# ESP32_radio_rev1_0.net
KiCad netlist of a schematic drawn in EAGLE
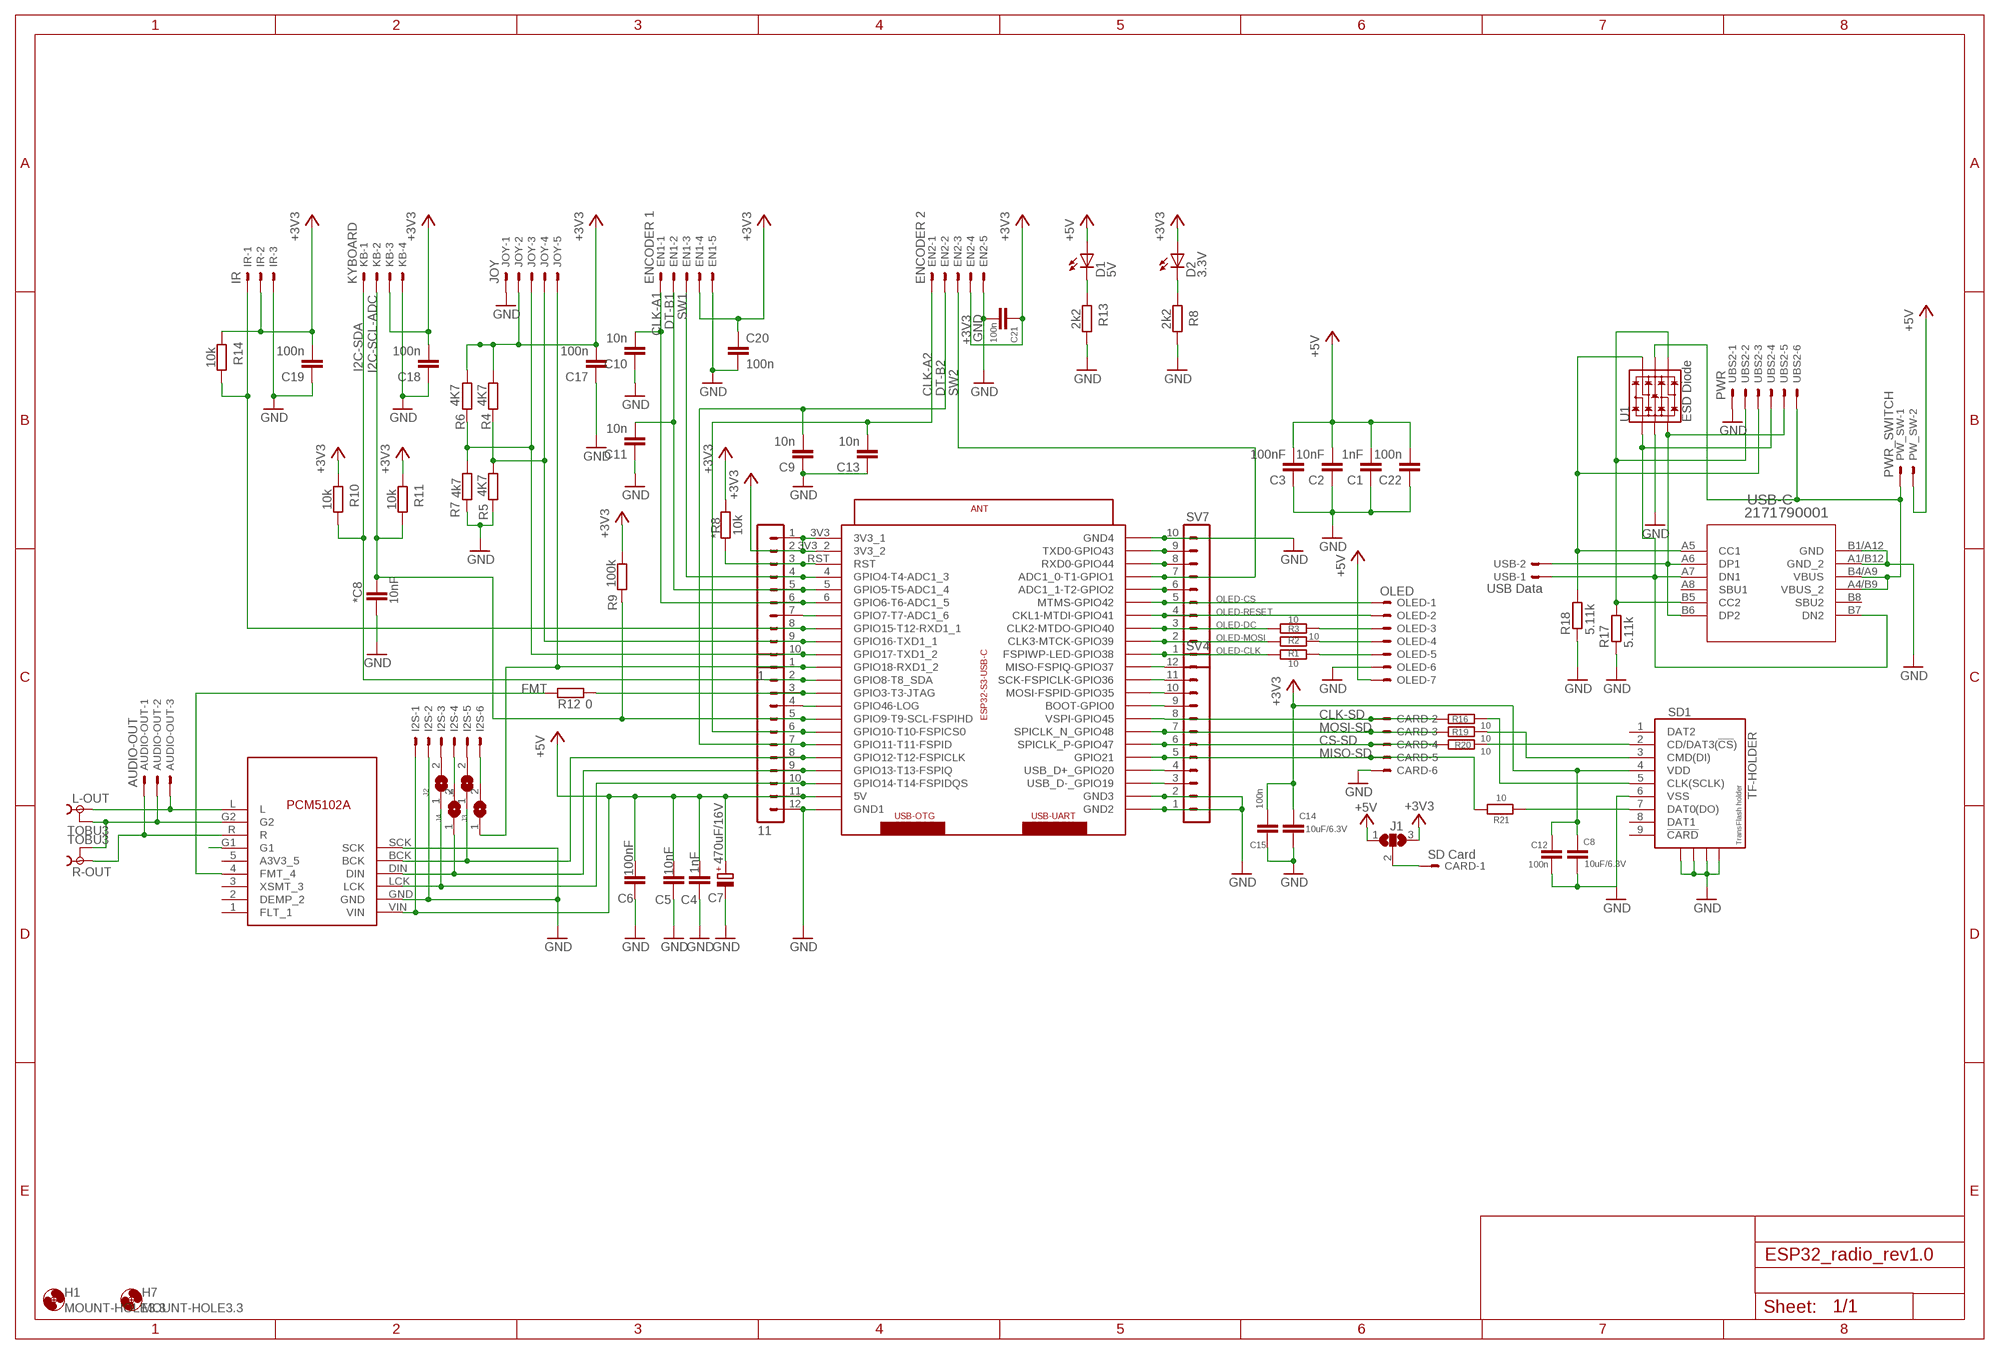
[diagram p0: schematic, sheet 1]

(export (version "E")
  (design (tool "Eeschema 10.0.6"))
  (components
    (comp (ref "*C8")
      (value "10nF")
      (footprint "eagle-import:C0603")
      (libsource (lib "eagle-import") (part "C-EUC0603"))
    )
    (comp (ref "*R8")
      (value "10k")
      (footprint "eagle-import:R0603")
      (libsource (lib "eagle-import") (part "R-EU_R0603"))
    )
    (comp (ref "1")
      (value "MA10-1")
      (footprint "eagle-import:MA10-1")
      (libsource (lib "eagle-import") (part "MA10-1"))
    )
    (comp (ref "11")
      (value "MA12-1")
      (footprint "eagle-import:MA12-1")
      (libsource (lib "eagle-import") (part "MA12-1"))
    )
    (comp (ref "AUDIO-OUT")
      (value "AUDIO-OUT")
      (footprint "eagle-import:JST-XH-03-PACKAGE-LONG-PAD")
      (libsource (lib "eagle-import") (part "JST-XH-03-PIN-LONG-PAD"))
    )
    (comp (ref "C1")
      (value "1nF")
      (footprint "eagle-import:C0603")
      (libsource (lib "eagle-import") (part "C-EUC0603"))
    )
    (comp (ref "C2")
      (value "10nF")
      (footprint "eagle-import:C0603")
      (libsource (lib "eagle-import") (part "C-EUC0603"))
    )
    (comp (ref "C3")
      (value "100nF")
      (footprint "eagle-import:C0603")
      (libsource (lib "eagle-import") (part "C-EUC0603"))
    )
    (comp (ref "C4")
      (value "1nF")
      (footprint "eagle-import:C0603")
      (libsource (lib "eagle-import") (part "C-EUC0603"))
    )
    (comp (ref "C5")
      (value "10nF")
      (footprint "eagle-import:C0603")
      (libsource (lib "eagle-import") (part "C-EUC0603"))
    )
    (comp (ref "C6")
      (value "100nF")
      (footprint "eagle-import:C0603")
      (libsource (lib "eagle-import") (part "C-EUC0603"))
    )
    (comp (ref "C7")
      (value "470uF/16V")
      (footprint "eagle-import:150CLZ-1010")
      (libsource (lib "eagle-import") (part "CPOL-EU150CLZ-1010"))
    )
    (comp (ref "C8")
      (value "10uF/6.3V")
      (footprint "eagle-import:C1210")
      (libsource (lib "eagle-import") (part "C-EUC1210"))
    )
    (comp (ref "C9")
      (value "10n")
      (footprint "eagle-import:C0603")
      (libsource (lib "eagle-import") (part "C-EUC0603"))
    )
    (comp (ref "C10")
      (value "10n")
      (footprint "eagle-import:C0603")
      (libsource (lib "eagle-import") (part "C-EUC0603"))
    )
    (comp (ref "C11")
      (value "10n")
      (footprint "eagle-import:C0603")
      (libsource (lib "eagle-import") (part "C-EUC0603"))
    )
    (comp (ref "C12")
      (value "100n")
      (footprint "eagle-import:C0603")
      (libsource (lib "eagle-import") (part "C-EUC0603"))
    )
    (comp (ref "C13")
      (value "10n")
      (footprint "eagle-import:C0603")
      (libsource (lib "eagle-import") (part "C-EUC0603"))
    )
    (comp (ref "C14")
      (value "10uF/6.3V")
      (footprint "eagle-import:C1210")
      (libsource (lib "eagle-import") (part "C-EUC1210"))
    )
    (comp (ref "C15")
      (value "100n")
      (footprint "eagle-import:C0603")
      (libsource (lib "eagle-import") (part "C-EUC0603"))
    )
    (comp (ref "C17")
      (value "100n")
      (footprint "eagle-import:C0603")
      (libsource (lib "eagle-import") (part "C-EUC0603"))
    )
    (comp (ref "C18")
      (value "100n")
      (footprint "eagle-import:C0603")
      (libsource (lib "eagle-import") (part "C-EUC0603"))
    )
    (comp (ref "C19")
      (value "100n")
      (footprint "eagle-import:C0603")
      (libsource (lib "eagle-import") (part "C-EUC0603"))
    )
    (comp (ref "C20")
      (value "100n")
      (footprint "eagle-import:C0603")
      (libsource (lib "eagle-import") (part "C-EUC0603"))
    )
    (comp (ref "C21")
      (value "100n")
      (footprint "eagle-import:C0603")
      (libsource (lib "eagle-import") (part "C-EUC0603"))
    )
    (comp (ref "C22")
      (value "100n")
      (footprint "eagle-import:C0603")
      (libsource (lib "eagle-import") (part "C-EUC0603"))
    )
    (comp (ref "CARD")
      (value "SD Card")
      (footprint "eagle-import:JST-XH-06-PACKAGE-LONG-PAD")
      (libsource (lib "eagle-import") (part "JST-XH-06-PIN-LONG-PAD"))
    )
    (comp (ref "D1")
      (value "5V")
      (footprint "eagle-import:CHIP-LED0805")
      (libsource (lib "eagle-import") (part "LEDCHIP-LED0805"))
    )
    (comp (ref "D2")
      (value "3.3V")
      (footprint "eagle-import:CHIP-LED0805")
      (libsource (lib "eagle-import") (part "LEDCHIP-LED0805"))
    )
    (comp (ref "EN1")
      (value "ENCODER 1")
      (footprint "eagle-import:JST-XH-05-PACKAGE-LONG-PAD")
      (libsource (lib "eagle-import") (part "JST-XH-05-PIN-LONG-PAD"))
    )
    (comp (ref "EN2")
      (value "ENCODER 2")
      (footprint "eagle-import:JST-XH-05-PACKAGE-LONG-PAD")
      (libsource (lib "eagle-import") (part "JST-XH-05-PIN-LONG-PAD"))
    )
    (comp (ref "H1")
      (value "MOUNT-HOLE3.3")
      (footprint "eagle-import:3,3")
      (libsource (lib "eagle-import") (part "MOUNT-HOLE3.3"))
    )
    (comp (ref "H7")
      (value "MOUNT-HOLE3.3")
      (footprint "eagle-import:3,3")
      (libsource (lib "eagle-import") (part "MOUNT-HOLE3.3"))
    )
    (comp (ref "I2S")
      (value "JST-XH-06-PIN-LONG-PAD")
      (footprint "eagle-import:JST-XH-06-PACKAGE-LONG-PAD")
      (libsource (lib "eagle-import") (part "JST-XH-06-PIN-LONG-PAD"))
    )
    (comp (ref "IR")
      (value "IR")
      (footprint "eagle-import:JST-XH-03-PACKAGE-LONG-PAD")
      (libsource (lib "eagle-import") (part "JST-XH-03-PIN-LONG-PAD"))
    )
    (comp (ref "J1")
      (value "SJ2W")
      (footprint "eagle-import:SJ_2")
      (libsource (lib "eagle-import") (part "SJ2W"))
    )
    (comp (ref "J2") (value "SJ") (footprint "eagle-import:SJ") (libsource (lib "eagle-import") (part "SJ")))
    (comp (ref "J3") (value "SJ") (footprint "eagle-import:SJ") (libsource (lib "eagle-import") (part "SJ")))
    (comp (ref "J4") (value "SJ") (footprint "eagle-import:SJ") (libsource (lib "eagle-import") (part "SJ")))
    (comp (ref "J5") (value "SJ") (footprint "eagle-import:SJ") (libsource (lib "eagle-import") (part "SJ")))
    (comp (ref "JOY")
      (value "JOY")
      (footprint "eagle-import:JST-XH-05-PACKAGE-LONG-PAD")
      (libsource (lib "eagle-import") (part "JST-XH-05-PIN-LONG-PAD"))
    )
    (comp (ref "KB")
      (value "KYBOARD")
      (footprint "eagle-import:JST-XH-04-PACKAGE-LONG-PAD")
      (libsource (lib "eagle-import") (part "JST-XH-04-PIN-LONG-PAD"))
    )
    (comp (ref "L-OUT")
      (value "TOBU3")
      (footprint "eagle-import:TOBU3")
      (fields (field (name "MF") "FARNELL") (field (name "MPN") "TOBU 3"))
      (libsource (lib "eagle-import") (part "TOBU3"))
    )
    (comp (ref "M2")
      (value "I2S_PCM_51XX_SOUNDCARD")
      (footprint "eagle-import:I2S_PCM_5100_SOUNDCARD")
      (libsource (lib "eagle-import") (part "I2S_PCM_51XX_SOUNDCARD"))
    )
    (comp (ref "OLED")
      (value "OLED")
      (footprint "eagle-import:JST-XH-07-PACKAGE-LONG-PAD")
      (libsource (lib "eagle-import") (part "JST-XH-07-PIN-LONG-PAD"))
    )
    (comp (ref "PW_SW")
      (value "PWR_SWITCH")
      (footprint "eagle-import:JST-XH-02-PACKAGE-LONG-PAD")
      (libsource (lib "eagle-import") (part "JST-XH-02-PIN-LONG-PAD"))
    )
    (comp (ref "R-OUT")
      (value "TOBU3")
      (footprint "eagle-import:TOBU3")
      (fields (field (name "MF") "FARNELL") (field (name "MPN") "TOBU 3"))
      (libsource (lib "eagle-import") (part "TOBU3"))
    )
    (comp (ref "R1")
      (value "10")
      (footprint "eagle-import:R0603")
      (libsource (lib "eagle-import") (part "R-EU_R0603"))
    )
    (comp (ref "R2")
      (value "10")
      (footprint "eagle-import:R0603")
      (libsource (lib "eagle-import") (part "R-EU_R0603"))
    )
    (comp (ref "R3")
      (value "10")
      (footprint "eagle-import:R0603")
      (libsource (lib "eagle-import") (part "R-EU_R0603"))
    )
    (comp (ref "R4")
      (value "4K7")
      (footprint "eagle-import:R0603")
      (libsource (lib "eagle-import") (part "R-EU_R0603"))
    )
    (comp (ref "R5")
      (value "4K7")
      (footprint "eagle-import:R0603")
      (libsource (lib "eagle-import") (part "R-EU_R0603"))
    )
    (comp (ref "R6")
      (value "4K7")
      (footprint "eagle-import:R0603")
      (libsource (lib "eagle-import") (part "R-EU_R0603"))
    )
    (comp (ref "R7")
      (value "4k7")
      (footprint "eagle-import:R0603")
      (libsource (lib "eagle-import") (part "R-EU_R0603"))
    )
    (comp (ref "R8")
      (value "2k2")
      (footprint "eagle-import:R0603")
      (libsource (lib "eagle-import") (part "R-EU_R0603"))
    )
    (comp (ref "R9")
      (value "100k")
      (footprint "eagle-import:R0603")
      (libsource (lib "eagle-import") (part "R-EU_R0603"))
    )
    (comp (ref "R10")
      (value "10k")
      (footprint "eagle-import:R0603")
      (libsource (lib "eagle-import") (part "R-EU_R0603"))
    )
    (comp (ref "R11")
      (value "10k")
      (footprint "eagle-import:R0603")
      (libsource (lib "eagle-import") (part "R-EU_R0603"))
    )
    (comp (ref "R12")
      (value "0")
      (footprint "eagle-import:R0603")
      (libsource (lib "eagle-import") (part "R-EU_R0603"))
    )
    (comp (ref "R13")
      (value "2k2")
      (footprint "eagle-import:R0603")
      (libsource (lib "eagle-import") (part "R-EU_R0603"))
    )
    (comp (ref "R14")
      (value "10k")
      (footprint "eagle-import:R0603")
      (libsource (lib "eagle-import") (part "R-EU_R0603"))
    )
    (comp (ref "R16")
      (value "10")
      (footprint "eagle-import:R0603")
      (libsource (lib "eagle-import") (part "R-EU_R0603"))
    )
    (comp (ref "R17")
      (value "5.11k")
      (footprint "eagle-import:R0603")
      (libsource (lib "eagle-import") (part "R-EU_R0603"))
    )
    (comp (ref "R18")
      (value "5.11k")
      (footprint "eagle-import:R0603")
      (libsource (lib "eagle-import") (part "R-EU_R0603"))
    )
    (comp (ref "R19")
      (value "10")
      (footprint "eagle-import:R0603")
      (libsource (lib "eagle-import") (part "R-EU_R0603"))
    )
    (comp (ref "R20")
      (value "10")
      (footprint "eagle-import:R0603")
      (libsource (lib "eagle-import") (part "R-EU_R0603"))
    )
    (comp (ref "R21")
      (value "10")
      (footprint "eagle-import:R0603")
      (libsource (lib "eagle-import") (part "R-EU_R0603"))
    )
    (comp (ref "SD1")
      (value "TF-HOLDER")
      (footprint "eagle-import:TF-PULL")
      (libsource (lib "eagle-import") (part "TF-HOLDER"))
    )
    (comp (ref "SV4")
      (value "MA12-1")
      (footprint "eagle-import:MA12-1")
      (libsource (lib "eagle-import") (part "MA12-1"))
    )
    (comp (ref "SV7")
      (value "MA10-1")
      (footprint "eagle-import:MA10-1")
      (libsource (lib "eagle-import") (part "con-lstb_MA10-1"))
    )
    (comp (ref "U$1")
      (value "ESP32-S3-USBC")
      (footprint "eagle-import:ESP32-S3-USBC")
      (libsource (lib "eagle-import") (part "ESP32-S3-USBC"))
    )
    (comp (ref "U1")
      (value "ESD Diode")
      (footprint "eagle-import:SOT-23-6")
      (libsource (lib "eagle-import") (part "TVS_DIODE_ARRAY_DT1042-04SO-7"))
    )
    (comp (ref "UBS2")
      (value "PWR")
      (footprint "eagle-import:JST-XH-06-PACKAGE-LONG-PAD")
      (libsource (lib "eagle-import") (part "JST-XH-06-PIN-LONG-PAD"))
    )
    (comp (ref "USB")
      (value "USB Data")
      (footprint "eagle-import:JST-XH-02-PACKAGE-LONG-PAD")
      (libsource (lib "eagle-import") (part "JST-XH-02-PIN-LONG-PAD"))
    )
    (comp (ref "USB-C")
      (value "2171790001")
      (footprint "eagle-import:2171790001_MOL")
      (fields
        (field (name "MANUFACTURER_PART_NUMBER") "USB4105-GF-A-120")
        (field (name "COPYRIGHT") "Copyright (C) 2025 GRo")
      )
      (libsource (lib "eagle-import") (part "2171790001"))
    )
  )
  (nets
    (net (code "1") (name "+3V3") (class "Default")
      (node (ref "*R8") (pin "1") (pinfunction "1_1") (pintype "passive"))
      (node (ref "1") (pin "1") (pinfunction "1_1") (pintype "passive"))
      (node (ref "1") (pin "2") (pinfunction "2_2") (pintype "passive"))
      (node (ref "C12") (pin "2") (pinfunction "2_2") (pintype "passive"))
      (node (ref "C14") (pin "1") (pinfunction "1_1") (pintype "passive"))
      (node (ref "C15") (pin "2") (pinfunction "2_2") (pintype "passive"))
      (node (ref "C17") (pin "2") (pinfunction "2_2") (pintype "passive"))
      (node (ref "C18") (pin "2") (pinfunction "2_2") (pintype "passive"))
      (node (ref "C19") (pin "2") (pinfunction "2_2") (pintype "passive"))
      (node (ref "C20") (pin "1") (pinfunction "1_1") (pintype "passive"))
      (node (ref "C21") (pin "1") (pinfunction "1_1") (pintype "passive"))
      (node (ref "C8") (pin "1") (pinfunction "1_1") (pintype "passive"))
      (node (ref "D2") (pin "A") (pinfunction "A_A") (pintype "passive"))
      (node (ref "EN1") (pin "4") (pinfunction "S_4") (pintype "passive"))
      (node (ref "EN2") (pin "4") (pinfunction "S_4") (pintype "passive"))
      (node (ref "IR") (pin "2") (pinfunction "S_2") (pintype "passive"))
      (node (ref "J1") (pin "3") (pinfunction "3_3") (pintype "passive"))
      (node (ref "JOY") (pin "2") (pinfunction "S_2") (pintype "passive"))
      (node (ref "KB") (pin "3") (pinfunction "S_3") (pintype "passive"))
      (node (ref "R10") (pin "2") (pinfunction "2_2") (pintype "passive"))
      (node (ref "R11") (pin "2") (pinfunction "2_2") (pintype "passive"))
      (node (ref "R14") (pin "2") (pinfunction "2_2") (pintype "passive"))
      (node (ref "R4") (pin "2") (pinfunction "2_2") (pintype "passive"))
      (node (ref "R6") (pin "2") (pinfunction "2_2") (pintype "passive"))
      (node (ref "R9") (pin "2") (pinfunction "2_2") (pintype "passive"))
      (node (ref "SD1") (pin "4") (pinfunction "VDD_4") (pintype "power_in"))
      (node (ref "U$1") (pin "3V3") (pinfunction "3V3_1_3V3") (pintype "power_in"))
      (node (ref "U$1") (pin "3V3_2") (pinfunction "3V3_2_3V3_2") (pintype "power_in"))
    )
    (net (code "2") (name "+5V") (class "Default")
      (node (ref "11") (pin "11") (pinfunction "11_11") (pintype "passive"))
      (node (ref "C1") (pin "2") (pinfunction "2_2") (pintype "passive"))
      (node (ref "C2") (pin "2") (pinfunction "2_2") (pintype "passive"))
      (node (ref "C22") (pin "2") (pinfunction "2_2") (pintype "passive"))
      (node (ref "C3") (pin "2") (pinfunction "2_2") (pintype "passive"))
      (node (ref "C4") (pin "2") (pinfunction "2_2") (pintype "passive"))
      (node (ref "C5") (pin "2") (pinfunction "2_2") (pintype "passive"))
      (node (ref "C6") (pin "2") (pinfunction "2_2") (pintype "passive"))
      (node (ref "C7") (pin "+") (pinfunction "+_+") (pintype "passive"))
      (node (ref "D1") (pin "A") (pinfunction "A_A") (pintype "passive"))
      (node (ref "I2S") (pin "1") (pinfunction "S_1") (pintype "passive"))
      (node (ref "J1") (pin "1") (pinfunction "1_1") (pintype "passive"))
      (node (ref "M2") (pin "VIN") (pinfunction "VIN_VIN") (pintype "bidirectional"))
      (node (ref "OLED") (pin "7") (pinfunction "S_7") (pintype "passive"))
      (node (ref "PW_SW") (pin "2") (pinfunction "S_2") (pintype "passive"))
      (node (ref "U$1") (pin "5V") (pinfunction "5V_5V") (pintype "power_in"))
    )
    (net (code "3") (name "/CLK-A1") (class "Default")
      (node (ref "1") (pin "6") (pinfunction "6_6") (pintype "passive"))
      (node (ref "C10") (pin "2") (pinfunction "2_2") (pintype "passive"))
      (node (ref "EN1") (pin "1") (pinfunction "S_1") (pintype "passive"))
      (node (ref "U$1") (pin "6") (pinfunction "GPIO6-T6-ADC1_5_6") (pintype "bidirectional"))
    )
    (net (code "4") (name "/CLK-A2") (class "Default")
      (node (ref "11") (pin "6") (pinfunction "6_6") (pintype "passive"))
      (node (ref "C13") (pin "2") (pinfunction "2_2") (pintype "passive"))
      (node (ref "EN2") (pin "1") (pinfunction "S_1") (pintype "passive"))
      (node (ref "U$1") (pin "10") (pinfunction "GPIO10-T10-FSPICS0_10") (pintype "bidirectional"))
    )
    (net (code "5") (name "/CLK-SD") (class "Default")
      (node (ref "CARD") (pin "2") (pinfunction "S_2") (pintype "passive"))
      (node (ref "R16") (pin "1") (pinfunction "1_1") (pintype "passive"))
      (node (ref "SV4") (pin "8") (pinfunction "8_8") (pintype "passive"))
      (node (ref "U$1") (pin "45") (pinfunction "VSPI-GPIO45_45") (pintype "bidirectional"))
    )
    (net (code "6") (name "/CS-SD") (class "Default")
      (node (ref "CARD") (pin "4") (pinfunction "S_4") (pintype "passive"))
      (node (ref "R20") (pin "1") (pinfunction "1_1") (pintype "passive"))
      (node (ref "SV4") (pin "6") (pinfunction "6_6") (pintype "passive"))
      (node (ref "U$1") (pin "47") (pinfunction "SPICLK_P-GPIO47_47") (pintype "bidirectional"))
    )
    (net (code "7") (name "/DT-B1") (class "Default")
      (node (ref "1") (pin "5") (pinfunction "5_5") (pintype "passive"))
      (node (ref "C11") (pin "2") (pinfunction "2_2") (pintype "passive"))
      (node (ref "EN1") (pin "2") (pinfunction "S_2") (pintype "passive"))
      (node (ref "U$1") (pin "5") (pinfunction "GPIO5-T5-ADC1_4_5") (pintype "bidirectional"))
    )
    (net (code "8") (name "/DT-B2") (class "Default")
      (node (ref "11") (pin "7") (pinfunction "7_7") (pintype "passive"))
      (node (ref "C9") (pin "2") (pinfunction "2_2") (pintype "passive"))
      (node (ref "EN2") (pin "2") (pinfunction "S_2") (pintype "passive"))
      (node (ref "U$1") (pin "11") (pinfunction "GPIO11-T11-FSPID_11") (pintype "bidirectional"))
    )
    (net (code "9") (name "/FMT") (class "Default")
      (node (ref "M2") (pin "4") (pinfunction "FMT_4_4") (pintype "bidirectional"))
      (node (ref "R12") (pin "2") (pinfunction "2_2") (pintype "passive"))
    )
    (net (code "10") (name "/I2C-SCL-ADC") (class "Default")
      (node (ref "*C8") (pin "1") (pinfunction "1_1") (pintype "passive"))
      (node (ref "11") (pin "5") (pinfunction "5_5") (pintype "passive"))
      (node (ref "KB") (pin "2") (pinfunction "S_2") (pintype "passive"))
      (node (ref "R11") (pin "1") (pinfunction "1_1") (pintype "passive"))
      (node (ref "R9") (pin "1") (pinfunction "1_1") (pintype "passive"))
      (node (ref "U$1") (pin "9") (pinfunction "GPIO9-T9-SCL-FSPIHD_9") (pintype "bidirectional"))
    )
    (net (code "11") (name "/I2C-SDA") (class "Default")
      (node (ref "11") (pin "2") (pinfunction "2_2") (pintype "passive"))
      (node (ref "KB") (pin "1") (pinfunction "S_1") (pintype "passive"))
      (node (ref "R10") (pin "1") (pinfunction "1_1") (pintype "passive"))
      (node (ref "U$1") (pin "8") (pinfunction "GPIO8-T8_SDA_8") (pintype "bidirectional"))
    )
    (net (code "12") (name "/MISO-SD") (class "Default")
      (node (ref "CARD") (pin "5") (pinfunction "S_5") (pintype "passive"))
      (node (ref "R21") (pin "1") (pinfunction "1_1") (pintype "passive"))
      (node (ref "SV4") (pin "5") (pinfunction "5_5") (pintype "passive"))
      (node (ref "U$1") (pin "21") (pinfunction "GPIO21_21") (pintype "bidirectional"))
    )
    (net (code "13") (name "/MOSI-SD") (class "Default")
      (node (ref "CARD") (pin "3") (pinfunction "S_3") (pintype "passive"))
      (node (ref "R19") (pin "1") (pinfunction "1_1") (pintype "passive"))
      (node (ref "SV4") (pin "7") (pinfunction "7_7") (pintype "passive"))
      (node (ref "U$1") (pin "48") (pinfunction "SPICLK_N_GPIO48_48") (pintype "bidirectional"))
    )
    (net (code "14") (name "/OLED-CLK") (class "Default")
      (node (ref "R1") (pin "1") (pinfunction "1_1") (pintype "passive"))
      (node (ref "SV7") (pin "1") (pinfunction "1_1") (pintype "passive"))
      (node (ref "U$1") (pin "38") (pinfunction "FSPIWP-LED-GPIO38_38") (pintype "bidirectional"))
    )
    (net (code "15") (name "/OLED-CS") (class "Default")
      (node (ref "OLED") (pin "1") (pinfunction "S_1") (pintype "passive"))
      (node (ref "SV7") (pin "5") (pinfunction "5_5") (pintype "passive"))
      (node (ref "U$1") (pin "42") (pinfunction "MTMS-GPIO42_42") (pintype "bidirectional"))
    )
    (net (code "16") (name "/OLED-DC") (class "Default")
      (node (ref "R3") (pin "1") (pinfunction "1_1") (pintype "passive"))
      (node (ref "SV7") (pin "3") (pinfunction "3_3") (pintype "passive"))
      (node (ref "U$1") (pin "40") (pinfunction "CLK2-MTDO-GPIO40_40") (pintype "bidirectional"))
    )
    (net (code "17") (name "/OLED-MOSI") (class "Default")
      (node (ref "R2") (pin "1") (pinfunction "1_1") (pintype "passive"))
      (node (ref "SV7") (pin "2") (pinfunction "2_2") (pintype "passive"))
      (node (ref "U$1") (pin "39") (pinfunction "CLK3-MTCK-GPIO39_39") (pintype "bidirectional"))
    )
    (net (code "18") (name "/OLED-RESET") (class "Default")
      (node (ref "OLED") (pin "2") (pinfunction "S_2") (pintype "passive"))
      (node (ref "SV7") (pin "4") (pinfunction "4_4") (pintype "passive"))
      (node (ref "U$1") (pin "41") (pinfunction "CKL1-MTDI-GPIO41_41") (pintype "bidirectional"))
    )
    (net (code "19") (name "/SW1") (class "Default")
      (node (ref "1") (pin "4") (pinfunction "4_4") (pintype "passive"))
      (node (ref "EN1") (pin "3") (pinfunction "S_3") (pintype "passive"))
      (node (ref "U$1") (pin "4") (pinfunction "GPIO4-T4-ADC1_3_4") (pintype "bidirectional"))
    )
    (net (code "20") (name "/SW2") (class "Default")
      (node (ref "EN2") (pin "3") (pinfunction "S_3") (pintype "passive"))
      (node (ref "SV7") (pin "7") (pinfunction "7_7") (pintype "passive"))
      (node (ref "U$1") (pin "1") (pinfunction "ADC1_0-T1-GPIO1_1") (pintype "bidirectional"))
    )
    (net (code "21") (name "GND") (class "Default")
      (node (ref "*C8") (pin "2") (pinfunction "2_2") (pintype "passive"))
      (node (ref "11") (pin "12") (pinfunction "12_12") (pintype "passive"))
      (node (ref "C1") (pin "1") (pinfunction "1_1") (pintype "passive"))
      (node (ref "C10") (pin "1") (pinfunction "1_1") (pintype "passive"))
      (node (ref "C11") (pin "1") (pinfunction "1_1") (pintype "passive"))
      (node (ref "C12") (pin "1") (pinfunction "1_1") (pintype "passive"))
      (node (ref "C13") (pin "1") (pinfunction "1_1") (pintype "passive"))
      (node (ref "C14") (pin "2") (pinfunction "2_2") (pintype "passive"))
      (node (ref "C15") (pin "1") (pinfunction "1_1") (pintype "passive"))
      (node (ref "C17") (pin "1") (pinfunction "1_1") (pintype "passive"))
      (node (ref "C18") (pin "1") (pinfunction "1_1") (pintype "passive"))
      (node (ref "C19") (pin "1") (pinfunction "1_1") (pintype "passive"))
      (node (ref "C2") (pin "1") (pinfunction "1_1") (pintype "passive"))
      (node (ref "C20") (pin "2") (pinfunction "2_2") (pintype "passive"))
      (node (ref "C21") (pin "2") (pinfunction "2_2") (pintype "passive"))
      (node (ref "C22") (pin "1") (pinfunction "1_1") (pintype "passive"))
      (node (ref "C3") (pin "1") (pinfunction "1_1") (pintype "passive"))
      (node (ref "C4") (pin "1") (pinfunction "1_1") (pintype "passive"))
      (node (ref "C5") (pin "1") (pinfunction "1_1") (pintype "passive"))
      (node (ref "C6") (pin "1") (pinfunction "1_1") (pintype "passive"))
      (node (ref "C7") (pin "-") (pinfunction "-_-") (pintype "passive"))
      (node (ref "C8") (pin "2") (pinfunction "2_2") (pintype "passive"))
      (node (ref "C9") (pin "1") (pinfunction "1_1") (pintype "passive"))
      (node (ref "CARD") (pin "6") (pinfunction "S_6") (pintype "passive"))
      (node (ref "EN1") (pin "5") (pinfunction "S_5") (pintype "passive"))
      (node (ref "EN2") (pin "5") (pinfunction "S_5") (pintype "passive"))
      (node (ref "I2S") (pin "2") (pinfunction "S_2") (pintype "passive"))
      (node (ref "IR") (pin "3") (pinfunction "S_3") (pintype "passive"))
      (node (ref "JOY") (pin "1") (pinfunction "S_1") (pintype "passive"))
      (node (ref "KB") (pin "4") (pinfunction "S_4") (pintype "passive"))
      (node (ref "M2") (pin "GND") (pinfunction "GND_GND") (pintype "bidirectional"))
      (node (ref "M2") (pin "SCK") (pinfunction "SCK_SCK") (pintype "bidirectional"))
      (node (ref "OLED") (pin "6") (pinfunction "S_6") (pintype "passive"))
      (node (ref "R13") (pin "1") (pinfunction "1_1") (pintype "passive"))
      (node (ref "R17") (pin "1") (pinfunction "1_1") (pintype "passive"))
      (node (ref "R18") (pin "1") (pinfunction "1_1") (pintype "passive"))
      (node (ref "R5") (pin "1") (pinfunction "1_1") (pintype "passive"))
      (node (ref "R7") (pin "1") (pinfunction "1_1") (pintype "passive"))
      (node (ref "R8") (pin "1") (pinfunction "1_1") (pintype "passive"))
      (node (ref "SD1") (pin "6") (pinfunction "VSS_6") (pintype "power_in"))
      (node (ref "SD1") (pin "S1") (pinfunction "S1_S1") (pintype "passive"))
      (node (ref "SD1") (pin "S2") (pinfunction "S2_S2") (pintype "passive"))
      (node (ref "SD1") (pin "S3") (pinfunction "S3_S3") (pintype "passive"))
      (node (ref "SD1") (pin "S4") (pinfunction "S4_S4") (pintype "passive"))
      (node (ref "SV4") (pin "1") (pinfunction "1_1") (pintype "passive"))
      (node (ref "SV4") (pin "2") (pinfunction "2_2") (pintype "passive"))
      (node (ref "SV7") (pin "10") (pinfunction "10_10") (pintype "passive"))
      (node (ref "U$1") (pin "GND1") (pinfunction "GND1_GND1") (pintype "power_in"))
      (node (ref "U$1") (pin "GND2") (pinfunction "GND2_GND2") (pintype "power_in"))
      (node (ref "U$1") (pin "GND3") (pinfunction "GND3_GND3") (pintype "power_in"))
      (node (ref "U$1") (pin "GND4") (pinfunction "GND4_GND4") (pintype "power_in"))
      (node (ref "U1") (pin "2") (pinfunction "VSS_2") (pintype "bidirectional"))
      (node (ref "UBS2") (pin "1") (pinfunction "S_1") (pintype "passive"))
      (node (ref "USB-C") (pin "A1/B12") (pinfunction "GND_2_A1/B12") (pintype "passive"))
      (node (ref "USB-C") (pin "B1/A12") (pinfunction "GND_B1/A12") (pintype "passive"))
    )
    (net (code "22") (name "Net-(*R8-Pad2)") (class "Default")
      (node (ref "*R8") (pin "2") (pinfunction "2_2") (pintype "passive"))
      (node (ref "1") (pin "3") (pinfunction "3_3") (pintype "passive"))
      (node (ref "U$1") (pin "RST") (pinfunction "RST_RST") (pintype "bidirectional"))
    )
    (net (code "23") (name "Net-(AUDIO-OUTA-S)") (class "Default")
      (node (ref "AUDIO-OUT") (pin "1") (pinfunction "S_1") (pintype "passive"))
      (node (ref "M2") (pin "R") (pinfunction "R_R") (pintype "bidirectional"))
      (node (ref "R-OUT") (pin "1") (pinfunction "1_1") (pintype "passive"))
    )
    (net (code "24") (name "Net-(AUDIO-OUTB-S)") (class "Default")
      (node (ref "AUDIO-OUT") (pin "2") (pinfunction "S_2") (pintype "passive"))
      (node (ref "L-OUT") (pin "2") (pinfunction "2_2") (pintype "passive"))
      (node (ref "L-OUT") (pin "2@1") (pinfunction "2_2@1") (pintype "passive"))
      (node (ref "L-OUT") (pin "2@2") (pinfunction "2_2@2") (pintype "passive"))
      (node (ref "M2") (pin "G2") (pinfunction "G2_G2") (pintype "bidirectional"))
      (node (ref "R-OUT") (pin "2") (pinfunction "2_2") (pintype "passive"))
      (node (ref "R-OUT") (pin "2@1") (pinfunction "2_2@1") (pintype "passive"))
      (node (ref "R-OUT") (pin "2@2") (pinfunction "2_2@2") (pintype "passive"))
    )
    (net (code "25") (name "Net-(AUDIO-OUTC-S)") (class "Default")
      (node (ref "AUDIO-OUT") (pin "3") (pinfunction "S_3") (pintype "passive"))
      (node (ref "L-OUT") (pin "1") (pinfunction "1_1") (pintype "passive"))
      (node (ref "M2") (pin "L") (pinfunction "L_L") (pintype "bidirectional"))
    )
    (net (code "26") (name "Net-(CARDA-S)") (class "Default")
      (node (ref "CARD") (pin "1") (pinfunction "S_1") (pintype "passive"))
      (node (ref "J1") (pin "2") (pinfunction "2_2") (pintype "passive"))
    )
    (net (code "27") (name "Net-(D1-PadC)") (class "Default")
      (node (ref "D1") (pin "C") (pinfunction "C_C") (pintype "passive"))
      (node (ref "R13") (pin "2") (pinfunction "2_2") (pintype "passive"))
    )
    (net (code "28") (name "Net-(D2-PadC)") (class "Default")
      (node (ref "D2") (pin "C") (pinfunction "C_C") (pintype "passive"))
      (node (ref "R8") (pin "2") (pinfunction "2_2") (pintype "passive"))
    )
    (net (code "29") (name "Net-(I2SC-S)") (class "Default")
      (node (ref "I2S") (pin "3") (pinfunction "S_3") (pintype "passive"))
      (node (ref "J2") (pin "2") (pinfunction "2_2") (pintype "passive"))
    )
    (net (code "30") (name "Net-(I2SD-S)") (class "Default")
      (node (ref "I2S") (pin "4") (pinfunction "S_4") (pintype "passive"))
      (node (ref "J4") (pin "2") (pinfunction "2_2") (pintype "passive"))
    )
    (net (code "31") (name "Net-(I2SE-S)") (class "Default")
      (node (ref "I2S") (pin "5") (pinfunction "S_5") (pintype "passive"))
      (node (ref "J5") (pin "2") (pinfunction "2_2") (pintype "passive"))
    )
    (net (code "32") (name "Net-(I2SF-S)") (class "Default")
      (node (ref "I2S") (pin "6") (pinfunction "S_6") (pintype "passive"))
      (node (ref "J3") (pin "2") (pinfunction "2_2") (pintype "passive"))
    )
    (net (code "33") (name "Net-(IRA-S)") (class "Default")
      (node (ref "1") (pin "8") (pinfunction "8_8") (pintype "passive"))
      (node (ref "IR") (pin "1") (pinfunction "S_1") (pintype "passive"))
      (node (ref "R14") (pin "1") (pinfunction "1_1") (pintype "passive"))
      (node (ref "U$1") (pin "15") (pinfunction "GPIO15-T12-RXD1_1_15") (pintype "bidirectional"))
    )
    (net (code "34") (name "Net-(JOYC-S)") (class "Default")
      (node (ref "1") (pin "10") (pinfunction "10_10") (pintype "passive"))
      (node (ref "JOY") (pin "3") (pinfunction "S_3") (pintype "passive"))
      (node (ref "R6") (pin "1") (pinfunction "1_1") (pintype "passive"))
      (node (ref "R7") (pin "2") (pinfunction "2_2") (pintype "passive"))
      (node (ref "U$1") (pin "17") (pinfunction "GPIO17-TXD1_2_17") (pintype "bidirectional"))
    )
    (net (code "35") (name "Net-(JOYD-S)") (class "Default")
      (node (ref "1") (pin "9") (pinfunction "9_9") (pintype "passive"))
      (node (ref "JOY") (pin "4") (pinfunction "S_4") (pintype "passive"))
      (node (ref "R4") (pin "1") (pinfunction "1_1") (pintype "passive"))
      (node (ref "R5") (pin "2") (pinfunction "2_2") (pintype "passive"))
      (node (ref "U$1") (pin "16") (pinfunction "GPIO16-TXD1_1_16") (pintype "bidirectional"))
    )
    (net (code "36") (name "Net-(JOYE-S)") (class "Default")
      (node (ref "11") (pin "1") (pinfunction "1_1") (pintype "passive"))
      (node (ref "J3") (pin "1") (pinfunction "1_1") (pintype "passive"))
      (node (ref "JOY") (pin "5") (pinfunction "S_5") (pintype "passive"))
      (node (ref "U$1") (pin "18") (pinfunction "GPIO18-RXD1_2_18") (pintype "bidirectional"))
    )
    (net (code "37") (name "Net-(OLEDC-S)") (class "Default")
      (node (ref "OLED") (pin "3") (pinfunction "S_3") (pintype "passive"))
      (node (ref "R3") (pin "2") (pinfunction "2_2") (pintype "passive"))
    )
    (net (code "38") (name "Net-(OLEDD-S)") (class "Default")
      (node (ref "OLED") (pin "4") (pinfunction "S_4") (pintype "passive"))
      (node (ref "R2") (pin "2") (pinfunction "2_2") (pintype "passive"))
    )
    (net (code "39") (name "Net-(OLEDE-S)") (class "Default")
      (node (ref "OLED") (pin "5") (pinfunction "S_5") (pintype "passive"))
      (node (ref "R1") (pin "2") (pinfunction "2_2") (pintype "passive"))
    )
    (net (code "40") (name "Net-(PW_SWA-S)") (class "Default")
      (node (ref "PW_SW") (pin "1") (pinfunction "S_1") (pintype "passive"))
      (node (ref "U1") (pin "5") (pinfunction "VCC_5") (pintype "bidirectional"))
      (node (ref "UBS2") (pin "6") (pinfunction "S_6") (pintype "passive"))
      (node (ref "USB-C") (pin "A4/B9") (pinfunction "VBUS_2_A4/B9") (pintype "power_in"))
      (node (ref "USB-C") (pin "B4/A9") (pinfunction "VBUS_B4/A9") (pintype "power_in"))
    )
    (net (code "41") (name "Net-(SD1-CD{slash}DAT3(~{CS}))") (class "Default")
      (node (ref "R20") (pin "2") (pinfunction "2_2") (pintype "passive"))
      (node (ref "SD1") (pin "2") (pinfunction "CD/DAT3(~{CS})_2") (pintype "bidirectional"))
    )
    (net (code "42") (name "Net-(SD1-CLK(SCLK))") (class "Default")
      (node (ref "R16") (pin "2") (pinfunction "2_2") (pintype "passive"))
      (node (ref "SD1") (pin "5") (pinfunction "CLK(SCLK)_5") (pintype "input"))
    )
    (net (code "43") (name "Net-(SD1-CMD(DI))") (class "Default")
      (node (ref "R19") (pin "2") (pinfunction "2_2") (pintype "passive"))
      (node (ref "SD1") (pin "3") (pinfunction "CMD(DI)_3") (pintype "bidirectional"))
    )
    (net (code "44") (name "Net-(SD1-DAT0(DO))") (class "Default")
      (node (ref "R21") (pin "2") (pinfunction "2_2") (pintype "passive"))
      (node (ref "SD1") (pin "7") (pinfunction "DAT0(DO)_7") (pintype "bidirectional"))
    )
    (net (code "45") (name "Net-(U$1-ADC1_1-T2-GPIO2)") (class "Default")
      (node (ref "SV7") (pin "6") (pinfunction "6_6") (pintype "passive"))
      (node (ref "U$1") (pin "2") (pinfunction "ADC1_1-T2-GPIO2_2") (pintype "bidirectional"))
    )
    (net (code "46") (name "Net-(U$1-BOOT-GPIO0)") (class "Default")
      (node (ref "SV4") (pin "9") (pinfunction "9_9") (pintype "passive"))
      (node (ref "U$1") (pin "0") (pinfunction "BOOT-GPIO0_0") (pintype "bidirectional"))
    )
    (net (code "47") (name "Net-(U$1-GPIO3-T3-JTAG)") (class "Default")
      (node (ref "11") (pin "3") (pinfunction "3_3") (pintype "passive"))
      (node (ref "R12") (pin "1") (pinfunction "1_1") (pintype "passive"))
      (node (ref "U$1") (pin "3") (pinfunction "GPIO3-T3-JTAG_3") (pintype "bidirectional"))
    )
    (net (code "48") (name "Net-(U$1-GPIO7-T7-ADC1_6)") (class "Default")
      (node (ref "1") (pin "7") (pinfunction "7_7") (pintype "passive"))
      (node (ref "U$1") (pin "7") (pinfunction "GPIO7-T7-ADC1_6_7") (pintype "bidirectional"))
    )
    (net (code "49") (name "Net-(U$1-GPIO12-T12-FSPICLK)") (class "Default")
      (node (ref "11") (pin "8") (pinfunction "8_8") (pintype "passive"))
      (node (ref "J5") (pin "1") (pinfunction "1_1") (pintype "passive"))
      (node (ref "M2") (pin "BCK") (pinfunction "BCK_BCK") (pintype "bidirectional"))
      (node (ref "U$1") (pin "12") (pinfunction "GPIO12-T12-FSPICLK_12") (pintype "bidirectional"))
    )
    (net (code "50") (name "Net-(U$1-GPIO13-T13-FSPIQ)") (class "Default")
      (node (ref "11") (pin "9") (pinfunction "9_9") (pintype "passive"))
      (node (ref "J4") (pin "1") (pinfunction "1_1") (pintype "passive"))
      (node (ref "M2") (pin "DIN") (pinfunction "DIN_DIN") (pintype "bidirectional"))
      (node (ref "U$1") (pin "13") (pinfunction "GPIO13-T13-FSPIQ_13") (pintype "bidirectional"))
    )
    (net (code "51") (name "Net-(U$1-GPIO14-T14-FSPIDQS)") (class "Default")
      (node (ref "11") (pin "10") (pinfunction "10_10") (pintype "passive"))
      (node (ref "J2") (pin "1") (pinfunction "1_1") (pintype "passive"))
      (node (ref "M2") (pin "LCK") (pinfunction "LCK_LCK") (pintype "bidirectional"))
      (node (ref "U$1") (pin "14") (pinfunction "GPIO14-T14-FSPIDQS_14") (pintype "bidirectional"))
    )
    (net (code "52") (name "Net-(U$1-GPIO46-LOG)") (class "Default")
      (node (ref "11") (pin "4") (pinfunction "4_4") (pintype "passive"))
      (node (ref "U$1") (pin "46") (pinfunction "GPIO46-LOG_46") (pintype "bidirectional"))
    )
    (net (code "53") (name "Net-(U$1-MISO-FSPIQ-GPIO37)") (class "Default")
      (node (ref "SV4") (pin "12") (pinfunction "12_12") (pintype "passive"))
      (node (ref "U$1") (pin "37") (pinfunction "MISO-FSPIQ-GPIO37_37") (pintype "bidirectional"))
    )
    (net (code "54") (name "Net-(U$1-MOSI-FSPID-GPIO35)") (class "Default")
      (node (ref "SV4") (pin "10") (pinfunction "10_10") (pintype "passive"))
      (node (ref "U$1") (pin "35") (pinfunction "MOSI-FSPID-GPIO35_35") (pintype "bidirectional"))
    )
    (net (code "55") (name "Net-(U$1-RXD0-GPIO44)") (class "Default")
      (node (ref "SV7") (pin "8") (pinfunction "8_8") (pintype "passive"))
      (node (ref "U$1") (pin "44") (pinfunction "RXD0-GPIO44_44") (pintype "bidirectional"))
    )
    (net (code "56") (name "Net-(U$1-SCK-FSPICLK-GPIO36)") (class "Default")
      (node (ref "SV4") (pin "11") (pinfunction "11_11") (pintype "passive"))
      (node (ref "U$1") (pin "36") (pinfunction "SCK-FSPICLK-GPIO36_36") (pintype "bidirectional"))
    )
    (net (code "57") (name "Net-(U$1-TXD0-GPIO43)") (class "Default")
      (node (ref "SV7") (pin "9") (pinfunction "9_9") (pintype "passive"))
      (node (ref "U$1") (pin "43") (pinfunction "TXD0-GPIO43_43") (pintype "bidirectional"))
    )
    (net (code "58") (name "Net-(U$1-USB_D+_GPIO20)") (class "Default")
      (node (ref "SV4") (pin "4") (pinfunction "4_4") (pintype "passive"))
      (node (ref "U$1") (pin "20") (pinfunction "USB_D+_GPIO20_20") (pintype "bidirectional"))
    )
    (net (code "59") (name "Net-(U$1-USB_D-_GPIO19)") (class "Default")
      (node (ref "SV4") (pin "3") (pinfunction "3_3") (pintype "passive"))
      (node (ref "U$1") (pin "19") (pinfunction "USB_D-_GPIO19_19") (pintype "bidirectional"))
    )
    (net (code "60") (name "Net-(U1-IO1)") (class "Default")
      (node (ref "U1") (pin "1") (pinfunction "IO1_1") (pintype "bidirectional"))
      (node (ref "UBS2") (pin "4") (pinfunction "S_4") (pintype "passive"))
      (node (ref "USB") (pin "1") (pinfunction "S_1") (pintype "passive"))
      (node (ref "USB-C") (pin "A7") (pinfunction "DN1_A7") (pintype "bidirectional"))
      (node (ref "USB-C") (pin "B7") (pinfunction "DN2_B7") (pintype "bidirectional"))
    )
    (net (code "61") (name "Net-(U1-IO2)") (class "Default")
      (node (ref "U1") (pin "3") (pinfunction "IO2_3") (pintype "bidirectional"))
      (node (ref "UBS2") (pin "5") (pinfunction "S_5") (pintype "passive"))
      (node (ref "USB") (pin "2") (pinfunction "S_2") (pintype "passive"))
      (node (ref "USB-C") (pin "A6") (pinfunction "DP1_A6") (pintype "bidirectional"))
      (node (ref "USB-C") (pin "B6") (pinfunction "DP2_B6") (pintype "bidirectional"))
    )
    (net (code "62") (name "Net-(U1-IO3)") (class "Default")
      (node (ref "R17") (pin "2") (pinfunction "2_2") (pintype "passive"))
      (node (ref "U1") (pin "4") (pinfunction "IO3_4") (pintype "bidirectional"))
      (node (ref "UBS2") (pin "2") (pinfunction "S_2") (pintype "passive"))
      (node (ref "USB-C") (pin "B5") (pinfunction "CC2_B5") (pintype "bidirectional"))
    )
    (net (code "63") (name "Net-(U1-IO4)") (class "Default")
      (node (ref "R18") (pin "2") (pinfunction "2_2") (pintype "passive"))
      (node (ref "U1") (pin "6") (pinfunction "IO4_6") (pintype "bidirectional"))
      (node (ref "UBS2") (pin "3") (pinfunction "S_3") (pintype "passive"))
      (node (ref "USB-C") (pin "A5") (pinfunction "CC1_A5") (pintype "bidirectional"))
    )
    (net (code "64") (name "unconnected-(M2-A3V3_5-Pad5)") (class "Default")
      (node (ref "M2") (pin "5") (pinfunction "A3V3_5_5") (pintype "bidirectional"))
    )
    (net (code "65") (name "unconnected-(M2-DEMP_2-Pad2)") (class "Default")
      (node (ref "M2") (pin "2") (pinfunction "DEMP_2_2") (pintype "bidirectional"))
    )
    (net (code "66") (name "unconnected-(M2-FLT_1-Pad1)") (class "Default")
      (node (ref "M2") (pin "1") (pinfunction "FLT_1_1") (pintype "bidirectional"))
    )
    (net (code "67") (name "unconnected-(M2-PadG1)") (class "Default")
      (node (ref "M2") (pin "G1") (pinfunction "G1_G1") (pintype "bidirectional"))
    )
    (net (code "68") (name "unconnected-(M2-XSMT_3-Pad3)") (class "Default")
      (node (ref "M2") (pin "3") (pinfunction "XSMT_3_3") (pintype "bidirectional"))
    )
    (net (code "69") (name "unconnected-(SD1-DAT1-Pad8)") (class "Default")
      (node (ref "SD1") (pin "8") (pinfunction "DAT1_8") (pintype "bidirectional"))
    )
    (net (code "70") (name "unconnected-(SD1-DAT2-Pad1)") (class "Default")
      (node (ref "SD1") (pin "1") (pinfunction "DAT2_1") (pintype "bidirectional"))
    )
    (net (code "71") (name "unconnected-(SD1-~{CARD}-Pad9)") (class "Default")
      (node (ref "SD1") (pin "9") (pinfunction "~{CARD}_9") (pintype "passive"))
    )
    (net (code "72") (name "unconnected-(USB-C-SBU1-PadA8)") (class "Default")
      (node (ref "USB-C") (pin "A8") (pinfunction "SBU1_A8") (pintype "bidirectional"))
    )
    (net (code "73") (name "unconnected-(USB-C-SBU2-PadB8)") (class "Default")
      (node (ref "USB-C") (pin "B8") (pinfunction "SBU2_B8") (pintype "bidirectional"))
    )
  )
)
